# MIXR_Input_System_-_Buffer.net
KiCad netlist of a schematic drawn in Altium Designer
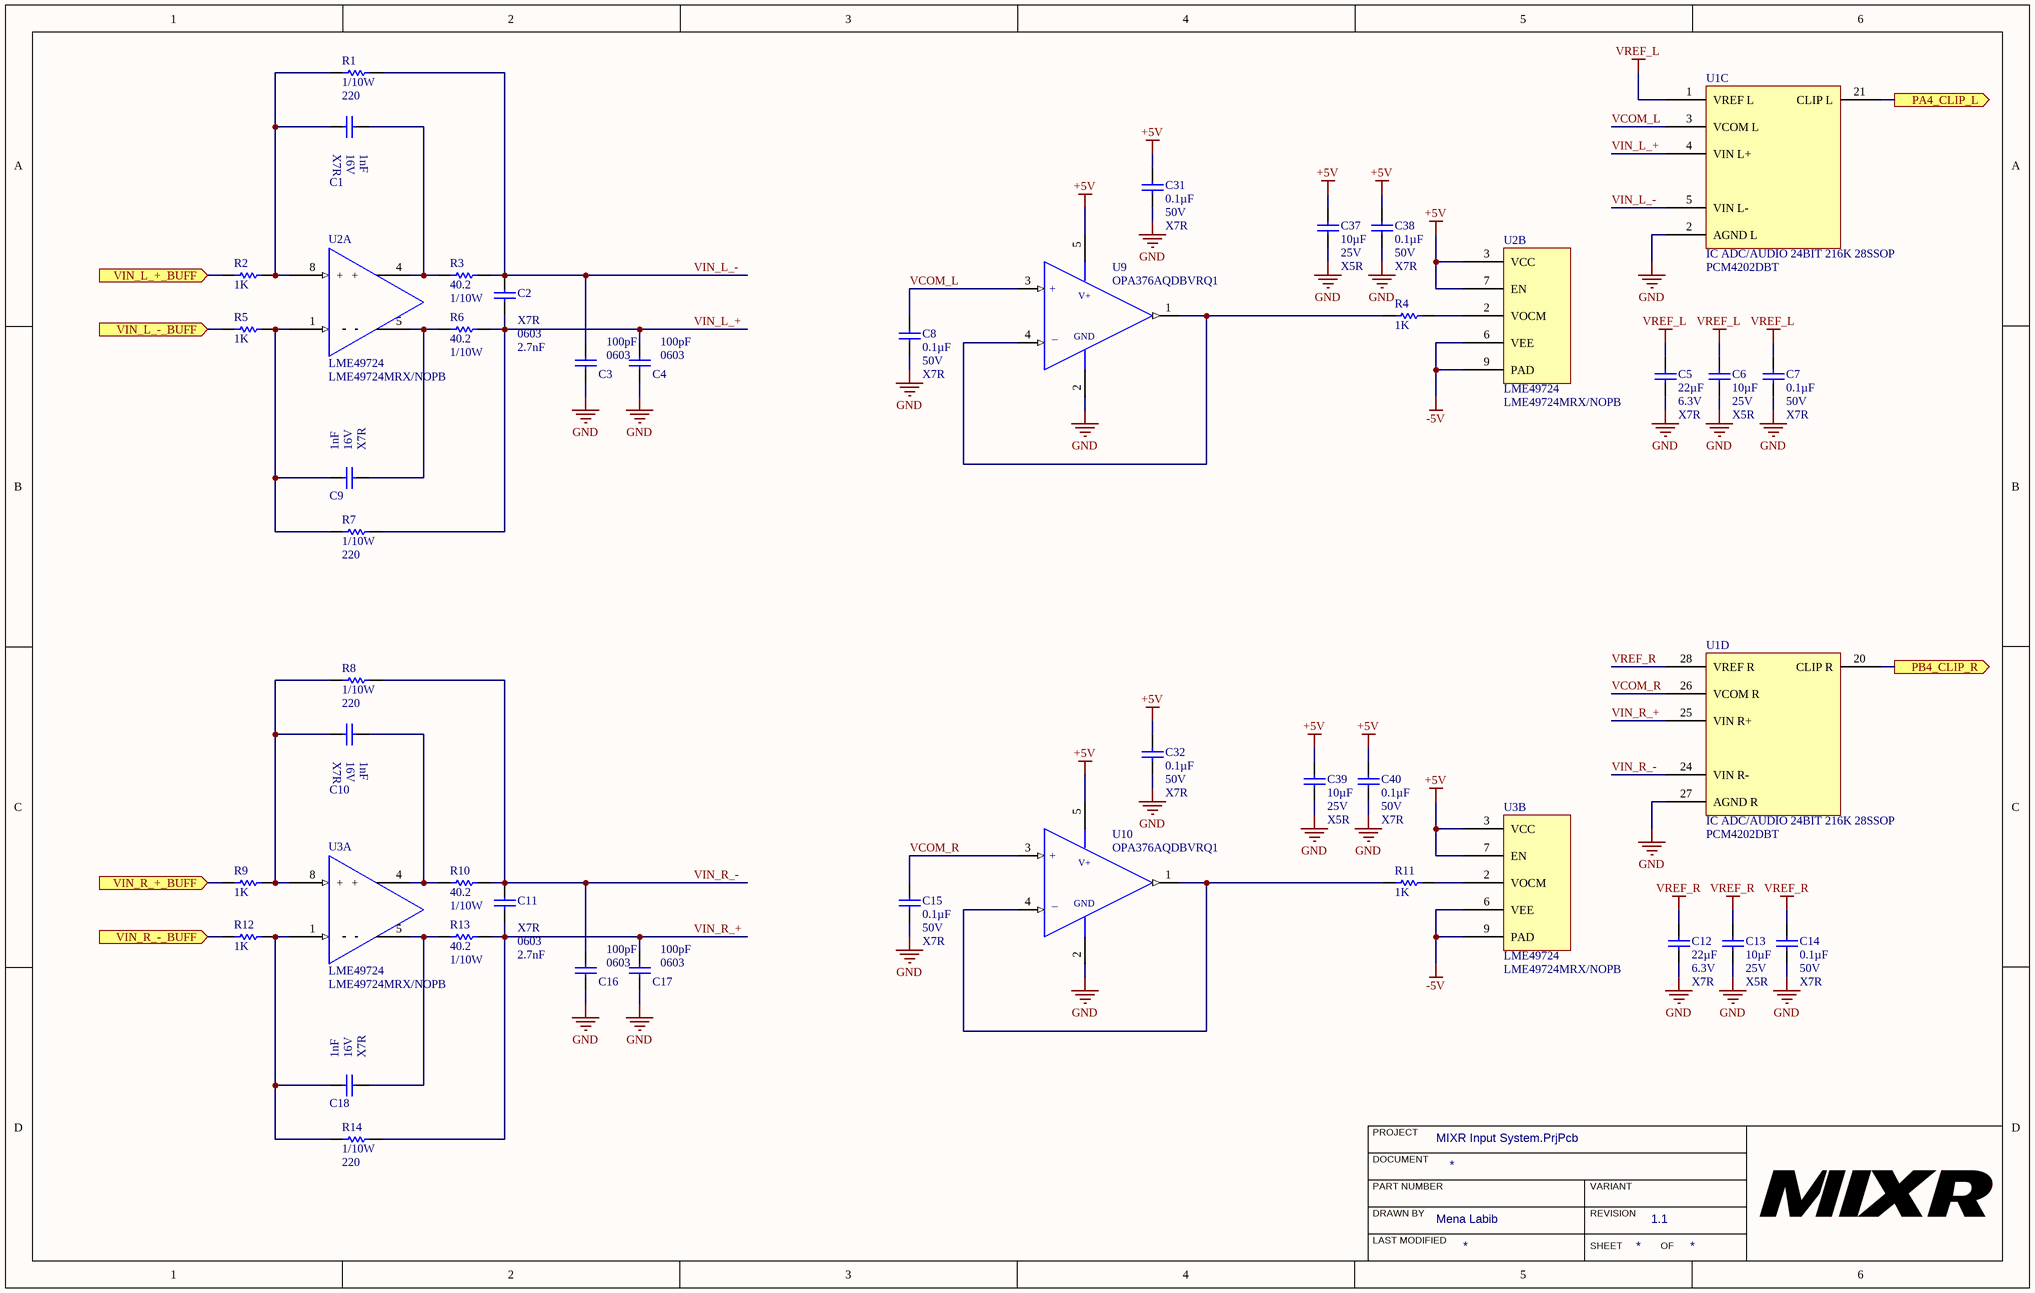
[diagram p0: MIXR Input System - Buffer.SchDoc]

(export (version "E")
  (design (tool "Eeschema 10.0.6"))
  (components
    (comp (ref "C1")
      (value "CAP CER 1NF 16V 10% X7R 0603")
      (footprint "CAP, 0603")
      (description "1000pF ±10% 16V Ceramic Capacitor X7R 0603 (1608 Metric)")
      (fields
        (field (name "MANUFACTURER") "KEMET")
        (field (name "MANUFACTURER PART NUMBER") "C0603C102K4RECAUTO")
      )
      (libsource (lib "Schematic Diagrams") (part "CAP CER 1NF 16V 10% X7R 0603"))
    )
    (comp (ref "C2")
      (value "CAP CER 2700PF 50V X7R 0603")
      (footprint "CAP, 0603")
      (description "2700pF ±10% 50V Ceramic Capacitor X7R 0603 (1608 Metric)")
      (fields
        (field (name "MANUFACTURER") "KEMET")
        (field (name "MANUFACTURER PART NUMBER") "C0603C272K5RACTU")
        (field (name "DIELECTRIC") "X7R")
        (field (name "CASE CODE (IMPERIAL)") "0603")
        (field (name "CAPACITANCE") "2.7nF")
      )
      (libsource (lib "Schematic Diagrams") (part "CAP CER 2700PF 50V X7R 0603"))
    )
    (comp (ref "C3")
      (value "CAP CER 100PF 50V C0G/NP0 0603")
      (footprint "CAP, 0603")
      (description "100pF ±1% 50V Ceramic Capacitor C0G, NP0 0603 (1608 Metric)")
      (fields
        (field (name "MANUFACTURER") "Kyocera AVX")
        (field (name "MANUFACTURER PART NUMBER") "06035A101FAT2A")
        (field (name "CASE CODE (IMPERIAL)") "0603")
        (field (name "CAPACITANCE") "100pF")
      )
      (libsource (lib "altium-import") (part "root_0_CAP CER 100PF 50V C0G/NP0 0603_"))
    )
    (comp (ref "C4")
      (value "CAP CER 100PF 50V C0G/NP0 0603")
      (footprint "CAP, 0603")
      (description "100pF ±1% 50V Ceramic Capacitor C0G, NP0 0603 (1608 Metric)")
      (fields
        (field (name "MANUFACTURER") "Kyocera AVX")
        (field (name "MANUFACTURER PART NUMBER") "06035A101FAT2A")
        (field (name "CASE CODE (IMPERIAL)") "0603")
        (field (name "CAPACITANCE") "100pF")
      )
      (libsource (lib "altium-import") (part "root_0_CAP CER 100PF 50V C0G/NP0 0603_"))
    )
    (comp (ref "C5")
      (value "CAP CER 22UF 6.3V ±10% X7R 1206")
      (footprint "CAP, 1206")
      (description "22µF ±10% 6.3V Ceramic Capacitor X7R 1206 (3216 Metric)")
      (fields
        (field (name "TOLERANCE") "±10%")
        (field (name "CAPACITANCE") "22µF")
        (field (name "VOLTAGE") "6.3V")
        (field (name "TEMPERATURE COEFFICIENT") "X7R")
      )
      (libsource (lib "altium-import") (part "root_0_CAP CER 22UF 6.3V ±10% X7R 1206_"))
    )
    (comp (ref "C6")
      (value "CAP CER 10uF 25V 20% X5R 0603")
      (footprint "CAP, 0603")
      (description "10µF ±20% 25V Ceramic Capacitor X5R 0603 (1608 Metric)")
      (fields
        (field (name "TOLERANCE") "±20%")
        (field (name "CAPACITANCE") "10µF")
        (field (name "VOLTAGE") "25V")
        (field (name "TEMPERATURE COEFFICIENT") "X5R")
      )
      (libsource (lib "Schematic Diagrams") (part "CAP CER 10uF 25V 20% X5R 0603"))
    )
    (comp (ref "C7")
      (value "CAP CER 0.1UF 50V 10% X7R 0603")
      (footprint "CAP, 0603")
      (description "0.10µF ±10% 50V Ceramic Capacitor X7R 0603 (1608 Metric)")
      (fields
        (field (name "TOLERANCE") "±10%")
        (field (name "CAPACITANCE") "0.1µF")
        (field (name "VOLTAGE") "50V")
        (field (name "TEMPERATURE COEFFICIENT") "X7R")
      )
      (libsource (lib "Schematic Diagrams") (part "CAP CER 0.1UF 50V 10% X7R 0603"))
    )
    (comp (ref "C8")
      (value "CAP CER 0.1UF 50V 10% X7R 0603")
      (footprint "CAP, 0603")
      (description "0.10µF ±10% 50V Ceramic Capacitor X7R 0603 (1608 Metric)")
      (fields
        (field (name "TOLERANCE") "±10%")
        (field (name "CAPACITANCE") "0.1µF")
        (field (name "VOLTAGE") "50V")
        (field (name "TEMPERATURE COEFFICIENT") "X7R")
      )
      (libsource (lib "Schematic Diagrams") (part "CAP CER 0.1UF 50V 10% X7R 0603"))
    )
    (comp (ref "C9")
      (value "CAP CER 1NF 16V 10% X7R 0603")
      (footprint "CAP, 0603")
      (description "1000pF ±10% 16V Ceramic Capacitor X7R 0603 (1608 Metric)")
      (fields
        (field (name "MANUFACTURER") "KEMET")
        (field (name "MANUFACTURER PART NUMBER") "C0603C102K4RECAUTO")
      )
      (libsource (lib "Schematic Diagrams") (part "CAP CER 1NF 16V 10% X7R 0603"))
    )
    (comp (ref "C10")
      (value "CAP CER 1NF 16V 10% X7R 0603")
      (footprint "CAP, 0603")
      (description "1000pF ±10% 16V Ceramic Capacitor X7R 0603 (1608 Metric)")
      (fields
        (field (name "MANUFACTURER") "KEMET")
        (field (name "MANUFACTURER PART NUMBER") "C0603C102K4RECAUTO")
      )
      (libsource (lib "Schematic Diagrams") (part "CAP CER 1NF 16V 10% X7R 0603"))
    )
    (comp (ref "C11")
      (value "CAP CER 2700PF 50V X7R 0603")
      (footprint "CAP, 0603")
      (description "2700pF ±10% 50V Ceramic Capacitor X7R 0603 (1608 Metric)")
      (fields
        (field (name "MANUFACTURER") "KEMET")
        (field (name "MANUFACTURER PART NUMBER") "C0603C272K5RACTU")
        (field (name "DIELECTRIC") "X7R")
        (field (name "CASE CODE (IMPERIAL)") "0603")
        (field (name "CAPACITANCE") "2.7nF")
      )
      (libsource (lib "Schematic Diagrams") (part "CAP CER 2700PF 50V X7R 0603"))
    )
    (comp (ref "C12")
      (value "CAP CER 22UF 6.3V ±10% X7R 1206")
      (footprint "CAP, 1206")
      (description "22µF ±10% 6.3V Ceramic Capacitor X7R 1206 (3216 Metric)")
      (fields
        (field (name "TOLERANCE") "±10%")
        (field (name "CAPACITANCE") "22µF")
        (field (name "VOLTAGE") "6.3V")
        (field (name "TEMPERATURE COEFFICIENT") "X7R")
      )
      (libsource (lib "altium-import") (part "root_0_CAP CER 22UF 6.3V ±10% X7R 1206_"))
    )
    (comp (ref "C13")
      (value "CAP CER 10uF 25V 20% X5R 0603")
      (footprint "CAP, 0603")
      (description "10µF ±20% 25V Ceramic Capacitor X5R 0603 (1608 Metric)")
      (fields
        (field (name "TOLERANCE") "±20%")
        (field (name "CAPACITANCE") "10µF")
        (field (name "VOLTAGE") "25V")
        (field (name "TEMPERATURE COEFFICIENT") "X5R")
      )
      (libsource (lib "Schematic Diagrams") (part "CAP CER 10uF 25V 20% X5R 0603"))
    )
    (comp (ref "C14")
      (value "CAP CER 0.1UF 50V 10% X7R 0603")
      (footprint "CAP, 0603")
      (description "0.10µF ±10% 50V Ceramic Capacitor X7R 0603 (1608 Metric)")
      (fields
        (field (name "TOLERANCE") "±10%")
        (field (name "CAPACITANCE") "0.1µF")
        (field (name "VOLTAGE") "50V")
        (field (name "TEMPERATURE COEFFICIENT") "X7R")
      )
      (libsource (lib "Schematic Diagrams") (part "CAP CER 0.1UF 50V 10% X7R 0603"))
    )
    (comp (ref "C15")
      (value "CAP CER 0.1UF 50V 10% X7R 0603")
      (footprint "CAP, 0603")
      (description "0.10µF ±10% 50V Ceramic Capacitor X7R 0603 (1608 Metric)")
      (fields
        (field (name "TOLERANCE") "±10%")
        (field (name "CAPACITANCE") "0.1µF")
        (field (name "VOLTAGE") "50V")
        (field (name "TEMPERATURE COEFFICIENT") "X7R")
      )
      (libsource (lib "Schematic Diagrams") (part "CAP CER 0.1UF 50V 10% X7R 0603"))
    )
    (comp (ref "C16")
      (value "CAP CER 100PF 50V C0G/NP0 0603")
      (footprint "CAP, 0603")
      (description "100pF ±1% 50V Ceramic Capacitor C0G, NP0 0603 (1608 Metric)")
      (fields
        (field (name "MANUFACTURER") "Kyocera AVX")
        (field (name "MANUFACTURER PART NUMBER") "06035A101FAT2A")
        (field (name "CASE CODE (IMPERIAL)") "0603")
        (field (name "CAPACITANCE") "100pF")
      )
      (libsource (lib "altium-import") (part "root_0_CAP CER 100PF 50V C0G/NP0 0603_"))
    )
    (comp (ref "C17")
      (value "CAP CER 100PF 50V C0G/NP0 0603")
      (footprint "CAP, 0603")
      (description "100pF ±1% 50V Ceramic Capacitor C0G, NP0 0603 (1608 Metric)")
      (fields
        (field (name "MANUFACTURER") "Kyocera AVX")
        (field (name "MANUFACTURER PART NUMBER") "06035A101FAT2A")
        (field (name "CASE CODE (IMPERIAL)") "0603")
        (field (name "CAPACITANCE") "100pF")
      )
      (libsource (lib "altium-import") (part "root_0_CAP CER 100PF 50V C0G/NP0 0603_"))
    )
    (comp (ref "C18")
      (value "CAP CER 1NF 16V 10% X7R 0603")
      (footprint "CAP, 0603")
      (description "1000pF ±10% 16V Ceramic Capacitor X7R 0603 (1608 Metric)")
      (fields
        (field (name "MANUFACTURER") "KEMET")
        (field (name "MANUFACTURER PART NUMBER") "C0603C102K4RECAUTO")
      )
      (libsource (lib "Schematic Diagrams") (part "CAP CER 1NF 16V 10% X7R 0603"))
    )
    (comp (ref "C31")
      (value "CAP CER 0.1UF 50V 10% X7R 0603")
      (footprint "CAP, 0603")
      (description "0.10µF ±10% 50V Ceramic Capacitor X7R 0603 (1608 Metric)")
      (fields
        (field (name "TOLERANCE") "±10%")
        (field (name "CAPACITANCE") "0.1µF")
        (field (name "VOLTAGE") "50V")
        (field (name "TEMPERATURE COEFFICIENT") "X7R")
      )
      (libsource (lib "Schematic Diagrams") (part "CAP CER 0.1UF 50V 10% X7R 0603"))
    )
    (comp (ref "C32")
      (value "CAP CER 0.1UF 50V 10% X7R 0603")
      (footprint "CAP, 0603")
      (description "0.10µF ±10% 50V Ceramic Capacitor X7R 0603 (1608 Metric)")
      (fields
        (field (name "TOLERANCE") "±10%")
        (field (name "CAPACITANCE") "0.1µF")
        (field (name "VOLTAGE") "50V")
        (field (name "TEMPERATURE COEFFICIENT") "X7R")
      )
      (libsource (lib "Schematic Diagrams") (part "CAP CER 0.1UF 50V 10% X7R 0603"))
    )
    (comp (ref "C37")
      (value "CAP CER 10uF 25V 20% X5R 0603")
      (footprint "CAP, 0603")
      (description "10µF ±20% 25V Ceramic Capacitor X5R 0603 (1608 Metric)")
      (fields
        (field (name "TOLERANCE") "±20%")
        (field (name "CAPACITANCE") "10µF")
        (field (name "VOLTAGE") "25V")
        (field (name "TEMPERATURE COEFFICIENT") "X5R")
      )
      (libsource (lib "Schematic Diagrams") (part "CAP CER 10uF 25V 20% X5R 0603"))
    )
    (comp (ref "C38")
      (value "CAP CER 0.1UF 50V 10% X7R 0603")
      (footprint "CAP, 0603")
      (description "0.10µF ±10% 50V Ceramic Capacitor X7R 0603 (1608 Metric)")
      (fields
        (field (name "TOLERANCE") "±10%")
        (field (name "CAPACITANCE") "0.1µF")
        (field (name "VOLTAGE") "50V")
        (field (name "TEMPERATURE COEFFICIENT") "X7R")
      )
      (libsource (lib "Schematic Diagrams") (part "CAP CER 0.1UF 50V 10% X7R 0603"))
    )
    (comp (ref "C39")
      (value "CAP CER 10uF 25V 20% X5R 0603")
      (footprint "CAP, 0603")
      (description "10µF ±20% 25V Ceramic Capacitor X5R 0603 (1608 Metric)")
      (fields
        (field (name "TOLERANCE") "±20%")
        (field (name "CAPACITANCE") "10µF")
        (field (name "VOLTAGE") "25V")
        (field (name "TEMPERATURE COEFFICIENT") "X5R")
      )
      (libsource (lib "Schematic Diagrams") (part "CAP CER 10uF 25V 20% X5R 0603"))
    )
    (comp (ref "C40")
      (value "CAP CER 0.1UF 50V 10% X7R 0603")
      (footprint "CAP, 0603")
      (description "0.10µF ±10% 50V Ceramic Capacitor X7R 0603 (1608 Metric)")
      (fields
        (field (name "TOLERANCE") "±10%")
        (field (name "CAPACITANCE") "0.1µF")
        (field (name "VOLTAGE") "50V")
        (field (name "TEMPERATURE COEFFICIENT") "X7R")
      )
      (libsource (lib "Schematic Diagrams") (part "CAP CER 0.1UF 50V 10% X7R 0603"))
    )
    (comp (ref "R1")
      (value "RES 220 OHM 1% 1/10W 0603")
      (footprint "RES, 0603")
      (description "220 Ohms ±1% 0.1W, 1/10W Chip Resistor 0603 (1608 Metric) Moisture Resistant Thick Film")
      (fields
        (field (name "MANUFACTURER") "Yageo")
        (field (name "MANUFACTURER PART NUMBER") "RC0603FR-07220RL")
        (field (name "POWER (WATTS)") "1/10W")
        (field (name "RESISTANCE") "220")
      )
      (libsource (lib "Schematic Diagrams") (part "RES 220 OHM 1% 1/10W 0603"))
    )
    (comp (ref "R2")
      (value "1K")
      (footprint "RES, 0603")
      (description "1k Ohm ±5% 0.1W, 1/10W Chip Resistor 0603 (1608 Metric)")
      (fields
        (field (name "MANUFACTURER") "Yageo")
        (field (name "MANUFACTURER PART NUMBER") "RC0603JR-071KL")
      )
      (libsource (lib "Schematic Diagrams") (part "RES 1K OHM 5% 1/10W 0603"))
    )
    (comp (ref "R3")
      (value "RES 40.2 OHM 0.5% 1/10W 0603")
      (footprint "RES, 0603")
      (description "RES SMD 40.2 OHM 0.5% 1/10W 0603")
      (fields
        (field (name "TOLERANCE") "±0.5%")
        (field (name "RESISTANCE") "40.2")
        (field (name "POWER") "1/10W")
      )
      (libsource (lib "Schematic Diagrams") (part "RES 40.2 OHM 0.5% 1/10W 0603"))
    )
    (comp (ref "R4")
      (value "1K")
      (footprint "RES, 0603")
      (description "1k Ohm ±5% 0.1W, 1/10W Chip Resistor 0603 (1608 Metric)")
      (fields
        (field (name "MANUFACTURER") "Yageo")
        (field (name "MANUFACTURER PART NUMBER") "RC0603JR-071KL")
      )
      (libsource (lib "altium-import") (part "root_1_RES 1K OHM 5% 1/10W 0603_"))
    )
    (comp (ref "R5")
      (value "1K")
      (footprint "RES, 0603")
      (description "1k Ohm ±5% 0.1W, 1/10W Chip Resistor 0603 (1608 Metric)")
      (fields
        (field (name "MANUFACTURER") "Yageo")
        (field (name "MANUFACTURER PART NUMBER") "RC0603JR-071KL")
      )
      (libsource (lib "Schematic Diagrams") (part "RES 1K OHM 5% 1/10W 0603"))
    )
    (comp (ref "R6")
      (value "RES 40.2 OHM 0.5% 1/10W 0603")
      (footprint "RES, 0603")
      (description "RES SMD 40.2 OHM 0.5% 1/10W 0603")
      (fields
        (field (name "TOLERANCE") "±0.5%")
        (field (name "RESISTANCE") "40.2")
        (field (name "POWER") "1/10W")
      )
      (libsource (lib "Schematic Diagrams") (part "RES 40.2 OHM 0.5% 1/10W 0603"))
    )
    (comp (ref "R7")
      (value "RES 220 OHM 1% 1/10W 0603")
      (footprint "RES, 0603")
      (description "220 Ohms ±1% 0.1W, 1/10W Chip Resistor 0603 (1608 Metric) Moisture Resistant Thick Film")
      (fields
        (field (name "MANUFACTURER") "Yageo")
        (field (name "MANUFACTURER PART NUMBER") "RC0603FR-07220RL")
        (field (name "POWER (WATTS)") "1/10W")
        (field (name "RESISTANCE") "220")
      )
      (libsource (lib "Schematic Diagrams") (part "RES 220 OHM 1% 1/10W 0603"))
    )
    (comp (ref "R8")
      (value "RES 220 OHM 1% 1/10W 0603")
      (footprint "RES, 0603")
      (description "220 Ohms ±1% 0.1W, 1/10W Chip Resistor 0603 (1608 Metric) Moisture Resistant Thick Film")
      (fields
        (field (name "MANUFACTURER") "Yageo")
        (field (name "MANUFACTURER PART NUMBER") "RC0603FR-07220RL")
        (field (name "POWER (WATTS)") "1/10W")
        (field (name "RESISTANCE") "220")
      )
      (libsource (lib "Schematic Diagrams") (part "RES 220 OHM 1% 1/10W 0603"))
    )
    (comp (ref "R9")
      (value "1K")
      (footprint "RES, 0603")
      (description "1k Ohm ±5% 0.1W, 1/10W Chip Resistor 0603 (1608 Metric)")
      (fields
        (field (name "MANUFACTURER") "Yageo")
        (field (name "MANUFACTURER PART NUMBER") "RC0603JR-071KL")
      )
      (libsource (lib "Schematic Diagrams") (part "RES 1K OHM 5% 1/10W 0603"))
    )
    (comp (ref "R10")
      (value "RES 40.2 OHM 0.5% 1/10W 0603")
      (footprint "RES, 0603")
      (description "RES SMD 40.2 OHM 0.5% 1/10W 0603")
      (fields
        (field (name "TOLERANCE") "±0.5%")
        (field (name "RESISTANCE") "40.2")
        (field (name "POWER") "1/10W")
      )
      (libsource (lib "Schematic Diagrams") (part "RES 40.2 OHM 0.5% 1/10W 0603"))
    )
    (comp (ref "R11")
      (value "1K")
      (footprint "RES, 0603")
      (description "1k Ohm ±5% 0.1W, 1/10W Chip Resistor 0603 (1608 Metric)")
      (fields
        (field (name "MANUFACTURER") "Yageo")
        (field (name "MANUFACTURER PART NUMBER") "RC0603JR-071KL")
      )
      (libsource (lib "altium-import") (part "root_1_RES 1K OHM 5% 1/10W 0603_"))
    )
    (comp (ref "R12")
      (value "1K")
      (footprint "RES, 0603")
      (description "1k Ohm ±5% 0.1W, 1/10W Chip Resistor 0603 (1608 Metric)")
      (fields
        (field (name "MANUFACTURER") "Yageo")
        (field (name "MANUFACTURER PART NUMBER") "RC0603JR-071KL")
      )
      (libsource (lib "Schematic Diagrams") (part "RES 1K OHM 5% 1/10W 0603"))
    )
    (comp (ref "R13")
      (value "RES 40.2 OHM 0.5% 1/10W 0603")
      (footprint "RES, 0603")
      (description "RES SMD 40.2 OHM 0.5% 1/10W 0603")
      (fields
        (field (name "TOLERANCE") "±0.5%")
        (field (name "RESISTANCE") "40.2")
        (field (name "POWER") "1/10W")
      )
      (libsource (lib "Schematic Diagrams") (part "RES 40.2 OHM 0.5% 1/10W 0603"))
    )
    (comp (ref "R14")
      (value "RES 220 OHM 1% 1/10W 0603")
      (footprint "RES, 0603")
      (description "220 Ohms ±1% 0.1W, 1/10W Chip Resistor 0603 (1608 Metric) Moisture Resistant Thick Film")
      (fields
        (field (name "MANUFACTURER") "Yageo")
        (field (name "MANUFACTURER PART NUMBER") "RC0603FR-07220RL")
        (field (name "POWER (WATTS)") "1/10W")
        (field (name "RESISTANCE") "220")
      )
      (libsource (lib "Schematic Diagrams") (part "RES 220 OHM 1% 1/10W 0603"))
    )
    (comp (ref "U1")
      (value "IC ADC/AUDIO 24BIT 216K 28SSOP")
      (footprint "IC ADC 24 BIT AUDIO 216 KHZ SSOP-28")
      (description "ADC, Audio 24 bit 216k DSP, PCM 28-SSOP")
      (fields
        (field (name "MANUFACTURER") "Texas Instruments")
        (field (name "MANUFACTURER PART NUMBER") "PCM4202DBT")
      )
      (libsource (lib "Schematic Diagrams") (part "IC ADC 24 BIT AUDIO 216KHZ SSOP-28"))
    )
    (comp (ref "U2")
      (value "LME49724")
      (footprint "IC OP AMP AUDIO LME49724 8-SOIC")
      (description "Audio Amplifier 1 Circuit Differential 8-SO PowerPad")
      (fields
        (field (name "MANUFACTURER") "TI National Semiconductor")
        (field (name "MANUFACTURER PART NUMBER") "LME49724MRX/NOPB")
      )
      (libsource (lib "Schematic Diagrams") (part "IC OP AMP AUDIO LME49724 8-SOIC"))
    )
    (comp (ref "U3")
      (value "LME49724")
      (footprint "IC OP AMP AUDIO LME49724 8-SOIC")
      (description "Audio Amplifier 1 Circuit Differential 8-SO PowerPad")
      (fields
        (field (name "MANUFACTURER") "TI National Semiconductor")
        (field (name "MANUFACTURER PART NUMBER") "LME49724MRX/NOPB")
      )
      (libsource (lib "Schematic Diagrams") (part "IC OP AMP AUDIO LME49724 8-SOIC"))
    )
    (comp (ref "U9")
      (value "IC OP AMP GEN PURPOSE RR 5.5MHZ SOT-23-5")
      (footprint "IC OP AMP GP RR 10MHZ SOT-23-5")
      (description "General Purpose Amplifier 1 Circuit Rail-to-Rail SOT-23-5")
      (fields
        (field (name "MANUFACTURER") "Texas Instruments")
        (field (name "MANUFACTURER PART NUMBER") "OPA376AQDBVRQ1")
      )
      (libsource (lib "Schematic Diagrams") (part "IC OP AMP GEN PURPOSE RR 5.5MHZ SOT-23-5"))
    )
    (comp (ref "U10")
      (value "IC OP AMP GEN PURPOSE RR 5.5MHZ SOT-23-5")
      (footprint "IC OP AMP GP RR 10MHZ SOT-23-5")
      (description "General Purpose Amplifier 1 Circuit Rail-to-Rail SOT-23-5")
      (fields
        (field (name "MANUFACTURER") "Texas Instruments")
        (field (name "MANUFACTURER PART NUMBER") "OPA376AQDBVRQ1")
      )
      (libsource (lib "Schematic Diagrams") (part "IC OP AMP GEN PURPOSE RR 5.5MHZ SOT-23-5"))
    )
  )
  (nets
    (net (code "1") (name "+5V") (class "Default")
      (node (ref "C31") (pin "1") (pinfunction "1_1") (pintype "passive"))
      (node (ref "C32") (pin "1") (pinfunction "1_1") (pintype "passive"))
      (node (ref "C37") (pin "1") (pinfunction "1_1") (pintype "passive"))
      (node (ref "C38") (pin "1") (pinfunction "1_1") (pintype "passive"))
      (node (ref "C39") (pin "1") (pinfunction "1_1") (pintype "passive"))
      (node (ref "C40") (pin "1") (pinfunction "1_1") (pintype "passive"))
      (node (ref "U10") (pin "5") (pinfunction "VDD_5") (pintype "power_in"))
      (node (ref "U2") (pin "3") (pinfunction "VCC_3") (pintype "passive"))
      (node (ref "U2") (pin "7") (pinfunction "EN_7") (pintype "passive"))
      (node (ref "U3") (pin "3") (pinfunction "VCC_3") (pintype "passive"))
      (node (ref "U3") (pin "7") (pinfunction "EN_7") (pintype "passive"))
      (node (ref "U9") (pin "5") (pinfunction "VDD_5") (pintype "power_in"))
    )
    (net (code "2") (name "-5V") (class "Default")
      (node (ref "U2") (pin "6") (pinfunction "VEE_6") (pintype "passive"))
      (node (ref "U2") (pin "9") (pinfunction "PAD_9") (pintype "passive"))
      (node (ref "U3") (pin "6") (pinfunction "VEE_6") (pintype "passive"))
      (node (ref "U3") (pin "9") (pinfunction "PAD_9") (pintype "passive"))
    )
    (net (code "3") (name "/PA4_CLIP_L") (class "Default")
      (node (ref "U1") (pin "21") (pinfunction "CLIP_L_21") (pintype "passive"))
    )
    (net (code "4") (name "/PB4_CLIP_R") (class "Default")
      (node (ref "U1") (pin "20") (pinfunction "CLIP_R_20") (pintype "passive"))
    )
    (net (code "5") (name "/VCOM_L") (class "Default")
      (node (ref "C8") (pin "1") (pinfunction "1_1") (pintype "passive"))
      (node (ref "U1") (pin "3") (pinfunction "VCOM_L_3") (pintype "passive"))
      (node (ref "U9") (pin "3") (pinfunction "+IN_3") (pintype "input"))
    )
    (net (code "6") (name "/VCOM_R") (class "Default")
      (node (ref "C15") (pin "1") (pinfunction "1_1") (pintype "passive"))
      (node (ref "U1") (pin "26") (pinfunction "VCOM_R_26") (pintype "passive"))
      (node (ref "U10") (pin "3") (pinfunction "+IN_3") (pintype "input"))
    )
    (net (code "7") (name "/VIN_L_+") (class "Default")
      (node (ref "C2") (pin "2") (pinfunction "2_2") (pintype "passive"))
      (node (ref "C4") (pin "1") (pinfunction "1_1") (pintype "passive"))
      (node (ref "R6") (pin "2") (pinfunction "2_2") (pintype "passive"))
      (node (ref "R7") (pin "1") (pinfunction "1_1") (pintype "passive"))
      (node (ref "U1") (pin "4") (pinfunction "VIN_L+_4") (pintype "passive"))
    )
    (net (code "8") (name "/VIN_L_+_BUFF") (class "Default")
      (node (ref "R2") (pin "1") (pinfunction "1_1") (pintype "passive"))
    )
    (net (code "9") (name "/VIN_L_-") (class "Default")
      (node (ref "C2") (pin "1") (pinfunction "1_1") (pintype "passive"))
      (node (ref "C3") (pin "1") (pinfunction "1_1") (pintype "passive"))
      (node (ref "R1") (pin "2") (pinfunction "2_2") (pintype "passive"))
      (node (ref "R3") (pin "2") (pinfunction "2_2") (pintype "passive"))
      (node (ref "U1") (pin "5") (pinfunction "VIN_L-_5") (pintype "passive"))
    )
    (net (code "10") (name "/VIN_L_-_BUFF") (class "Default")
      (node (ref "R5") (pin "1") (pinfunction "1_1") (pintype "passive"))
    )
    (net (code "11") (name "/VIN_R_+") (class "Default")
      (node (ref "C11") (pin "2") (pinfunction "2_2") (pintype "passive"))
      (node (ref "C17") (pin "1") (pinfunction "1_1") (pintype "passive"))
      (node (ref "R13") (pin "2") (pinfunction "2_2") (pintype "passive"))
      (node (ref "R14") (pin "1") (pinfunction "1_1") (pintype "passive"))
      (node (ref "U1") (pin "25") (pinfunction "VIN_R+_25") (pintype "passive"))
    )
    (net (code "12") (name "/VIN_R_+_BUFF") (class "Default")
      (node (ref "R9") (pin "1") (pinfunction "1_1") (pintype "passive"))
    )
    (net (code "13") (name "/VIN_R_-") (class "Default")
      (node (ref "C11") (pin "1") (pinfunction "1_1") (pintype "passive"))
      (node (ref "C16") (pin "1") (pinfunction "1_1") (pintype "passive"))
      (node (ref "R10") (pin "2") (pinfunction "2_2") (pintype "passive"))
      (node (ref "R8") (pin "2") (pinfunction "2_2") (pintype "passive"))
      (node (ref "U1") (pin "24") (pinfunction "VIN_R-_24") (pintype "passive"))
    )
    (net (code "14") (name "/VIN_R_-_BUFF") (class "Default")
      (node (ref "R12") (pin "1") (pinfunction "1_1") (pintype "passive"))
    )
    (net (code "15") (name "GND") (class "Default")
      (node (ref "C12") (pin "2") (pinfunction "2_2") (pintype "passive"))
      (node (ref "C13") (pin "2") (pinfunction "2_2") (pintype "passive"))
      (node (ref "C14") (pin "2") (pinfunction "2_2") (pintype "passive"))
      (node (ref "C15") (pin "2") (pinfunction "2_2") (pintype "passive"))
      (node (ref "C16") (pin "2") (pinfunction "2_2") (pintype "passive"))
      (node (ref "C17") (pin "2") (pinfunction "2_2") (pintype "passive"))
      (node (ref "C3") (pin "2") (pinfunction "2_2") (pintype "passive"))
      (node (ref "C31") (pin "2") (pinfunction "2_2") (pintype "passive"))
      (node (ref "C32") (pin "2") (pinfunction "2_2") (pintype "passive"))
      (node (ref "C37") (pin "2") (pinfunction "2_2") (pintype "passive"))
      (node (ref "C38") (pin "2") (pinfunction "2_2") (pintype "passive"))
      (node (ref "C39") (pin "2") (pinfunction "2_2") (pintype "passive"))
      (node (ref "C4") (pin "2") (pinfunction "2_2") (pintype "passive"))
      (node (ref "C40") (pin "2") (pinfunction "2_2") (pintype "passive"))
      (node (ref "C5") (pin "2") (pinfunction "2_2") (pintype "passive"))
      (node (ref "C6") (pin "2") (pinfunction "2_2") (pintype "passive"))
      (node (ref "C7") (pin "2") (pinfunction "2_2") (pintype "passive"))
      (node (ref "C8") (pin "2") (pinfunction "2_2") (pintype "passive"))
      (node (ref "U1") (pin "2") (pinfunction "AGND_L_2") (pintype "passive"))
      (node (ref "U1") (pin "27") (pinfunction "AGND_R_27") (pintype "passive"))
      (node (ref "U10") (pin "2") (pinfunction "VSS_2") (pintype "power_in"))
      (node (ref "U9") (pin "2") (pinfunction "VSS_2") (pintype "power_in"))
    )
    (net (code "16") (name "Net-(C1-Pad1)") (class "Default")
      (node (ref "C1") (pin "1") (pinfunction "1_1") (pintype "passive"))
      (node (ref "R3") (pin "1") (pinfunction "1_1") (pintype "passive"))
      (node (ref "U2") (pin "4") (pinfunction "+_4") (pintype "passive"))
    )
    (net (code "17") (name "Net-(C1-Pad2)") (class "Default")
      (node (ref "C1") (pin "2") (pinfunction "2_2") (pintype "passive"))
      (node (ref "R1") (pin "1") (pinfunction "1_1") (pintype "passive"))
      (node (ref "R2") (pin "2") (pinfunction "2_2") (pintype "passive"))
      (node (ref "U2") (pin "8") (pinfunction "+_8") (pintype "input"))
    )
    (net (code "18") (name "Net-(C9-Pad1)") (class "Default")
      (node (ref "C9") (pin "1") (pinfunction "1_1") (pintype "passive"))
      (node (ref "R5") (pin "2") (pinfunction "2_2") (pintype "passive"))
      (node (ref "R7") (pin "2") (pinfunction "2_2") (pintype "passive"))
      (node (ref "U2") (pin "1") (pinfunction "-_1") (pintype "input"))
    )
    (net (code "19") (name "Net-(C9-Pad2)") (class "Default")
      (node (ref "C9") (pin "2") (pinfunction "2_2") (pintype "passive"))
      (node (ref "R6") (pin "1") (pinfunction "1_1") (pintype "passive"))
      (node (ref "U2") (pin "5") (pinfunction "-_5") (pintype "passive"))
    )
    (net (code "20") (name "Net-(C10-Pad1)") (class "Default")
      (node (ref "C10") (pin "1") (pinfunction "1_1") (pintype "passive"))
      (node (ref "R10") (pin "1") (pinfunction "1_1") (pintype "passive"))
      (node (ref "U3") (pin "4") (pinfunction "+_4") (pintype "passive"))
    )
    (net (code "21") (name "Net-(C10-Pad2)") (class "Default")
      (node (ref "C10") (pin "2") (pinfunction "2_2") (pintype "passive"))
      (node (ref "R8") (pin "1") (pinfunction "1_1") (pintype "passive"))
      (node (ref "R9") (pin "2") (pinfunction "2_2") (pintype "passive"))
      (node (ref "U3") (pin "8") (pinfunction "+_8") (pintype "input"))
    )
    (net (code "22") (name "Net-(C18-Pad1)") (class "Default")
      (node (ref "C18") (pin "1") (pinfunction "1_1") (pintype "passive"))
      (node (ref "R12") (pin "2") (pinfunction "2_2") (pintype "passive"))
      (node (ref "R14") (pin "2") (pinfunction "2_2") (pintype "passive"))
      (node (ref "U3") (pin "1") (pinfunction "-_1") (pintype "input"))
    )
    (net (code "23") (name "Net-(C18-Pad2)") (class "Default")
      (node (ref "C18") (pin "2") (pinfunction "2_2") (pintype "passive"))
      (node (ref "R13") (pin "1") (pinfunction "1_1") (pintype "passive"))
      (node (ref "U3") (pin "5") (pinfunction "-_5") (pintype "passive"))
    )
    (net (code "24") (name "Net-(U2B-VOCM)") (class "Default")
      (node (ref "R4") (pin "2") (pinfunction "2_2") (pintype "passive"))
      (node (ref "U2") (pin "2") (pinfunction "VOCM_2") (pintype "passive"))
    )
    (net (code "25") (name "Net-(U3B-VOCM)") (class "Default")
      (node (ref "R11") (pin "2") (pinfunction "2_2") (pintype "passive"))
      (node (ref "U3") (pin "2") (pinfunction "VOCM_2") (pintype "passive"))
    )
    (net (code "26") (name "Net-(U9--IN)") (class "Default")
      (node (ref "R4") (pin "1") (pinfunction "1_1") (pintype "passive"))
      (node (ref "U9") (pin "1") (pinfunction "OUTPUT_1") (pintype "output"))
      (node (ref "U9") (pin "4") (pinfunction "-IN_4") (pintype "input"))
    )
    (net (code "27") (name "Net-(U10--IN)") (class "Default")
      (node (ref "R11") (pin "1") (pinfunction "1_1") (pintype "passive"))
      (node (ref "U10") (pin "1") (pinfunction "OUTPUT_1") (pintype "output"))
      (node (ref "U10") (pin "4") (pinfunction "-IN_4") (pintype "input"))
    )
    (net (code "28") (name "VREF_L") (class "Default")
      (node (ref "C5") (pin "1") (pinfunction "1_1") (pintype "passive"))
      (node (ref "C6") (pin "1") (pinfunction "1_1") (pintype "passive"))
      (node (ref "C7") (pin "1") (pinfunction "1_1") (pintype "passive"))
      (node (ref "U1") (pin "1") (pinfunction "VREF_L_1") (pintype "passive"))
    )
    (net (code "29") (name "VREF_R") (class "Default")
      (node (ref "C12") (pin "1") (pinfunction "1_1") (pintype "passive"))
      (node (ref "C13") (pin "1") (pinfunction "1_1") (pintype "passive"))
      (node (ref "C14") (pin "1") (pinfunction "1_1") (pintype "passive"))
      (node (ref "U1") (pin "28") (pinfunction "VREF_R_28") (pintype "passive"))
    )
  )
)
